# FM-Radio-Simple-Receiver-2.net
KiCad netlist of a schematic drawn in EAGLE
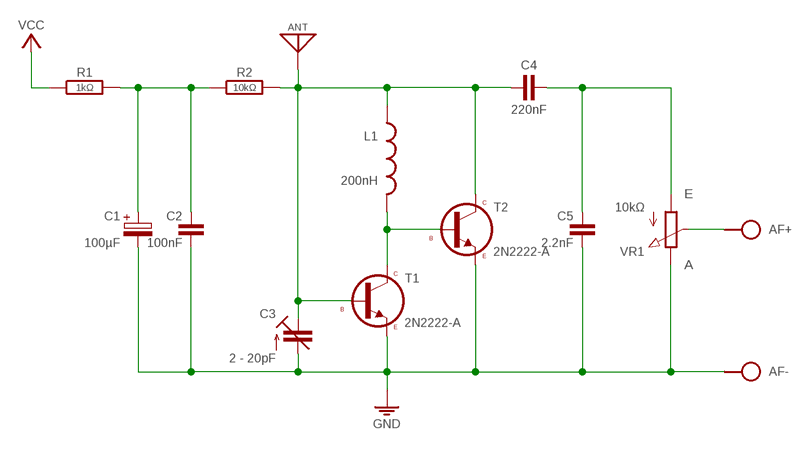
[diagram p0: schematic, sheet 1]

(export (version "E")
  (design (tool "Eeschema 10.0.6"))
  (components
    (comp (ref "AF")
      (value "SPAD+-+-")
      (footprint "eagle-import:SPAD+-")
      (libsource (lib "eagle-import") (part "SPAD+-+-"))
    )
    (comp (ref "ANT")
      (value "ANT")
      (footprint "eagle-import:SPAD")
      (libsource (lib "eagle-import") (part "ANT"))
    )
    (comp (ref "BAT")
      (value "VCC_GNDL")
      (footprint "eagle-import:SPAD-+")
      (libsource (lib "eagle-import") (part "VCC_GNDL"))
    )
    (comp (ref "C1")
      (value "100µF")
      (footprint "eagle-import:E2,5-5_V")
      (libsource (lib "eagle-import") (part "CPOLE2,5-5/V"))
    )
    (comp (ref "C2")
      (value "100nF")
      (footprint "eagle-import:C025-024X044")
      (libsource (lib "eagle-import") (part "C025-024X044"))
    )
    (comp (ref "C3")
      (value "2 - 20pF")
      (footprint "eagle-import:CTRIMBB")
      (libsource (lib "eagle-import") (part "C-TR-PH20127-2-1"))
    )
    (comp (ref "C4")
      (value "220nF")
      (footprint "eagle-import:C050-020X044")
      (libsource (lib "eagle-import") (part "C-H050-020X044"))
    )
    (comp (ref "C5")
      (value "2.2nF")
      (footprint "eagle-import:C050-020X036_V")
      (libsource (lib "eagle-import") (part "C050-020X036/V"))
    )
    (comp (ref "L1")
      (value "200nH")
      (footprint "eagle-import:L-10_10X")
      (libsource (lib "eagle-import") (part "L10/10X"))
    )
    (comp (ref "R1")
      (value "1kΩ")
      (footprint "eagle-import:0204_10-V")
      (libsource (lib "eagle-import") (part "R-H0204/10-V"))
    )
    (comp (ref "R2")
      (value "10kΩ")
      (footprint "eagle-import:0204_10-V")
      (libsource (lib "eagle-import") (part "R-H0204/10-V"))
    )
    (comp (ref "T1")
      (value "2N2222-A")
      (footprint "eagle-import:TO92-A")
      (libsource (lib "eagle-import") (part "2N2222-A"))
    )
    (comp (ref "T2")
      (value "2N2222-A")
      (footprint "eagle-import:TO92-A")
      (libsource (lib "eagle-import") (part "2N2222-A"))
    )
    (comp (ref "VR1")
      (value "10kΩ")
      (footprint "eagle-import:CONN-3P")
      (libsource (lib "eagle-import") (part "POT-3P"))
    )
  )
  (nets
    (net (code "1") (name "Net-(AFA-P$1)") (class "Default")
      (node (ref "AF") (pin "2") (pinfunction "P$1_2") (pintype "passive"))
      (node (ref "VR1") (pin "2") (pinfunction "S_2") (pintype "passive"))
    )
    (net (code "2") (name "Net-(AFB-P$1)") (class "Default")
      (node (ref "AF") (pin "1") (pinfunction "P$1_1") (pintype "passive"))
      (node (ref "BAT") (pin "1") (pinfunction "GND_1") (pintype "power_in"))
      (node (ref "C1") (pin "-") (pinfunction "-_-") (pintype "passive"))
      (node (ref "C2") (pin "2") (pinfunction "2_2") (pintype "passive"))
      (node (ref "C3") (pin "1") (pinfunction "A_1") (pintype "passive"))
      (node (ref "C5") (pin "2") (pinfunction "2_2") (pintype "passive"))
      (node (ref "T1") (pin "1") (pinfunction "E_1") (pintype "passive"))
      (node (ref "T2") (pin "1") (pinfunction "E_1") (pintype "passive"))
      (node (ref "VR1") (pin "3") (pinfunction "E_3") (pintype "passive"))
    )
    (net (code "3") (name "Net-(BATA-VCC)") (class "Default")
      (node (ref "BAT") (pin "2") (pinfunction "VCC_2") (pintype "power_in"))
      (node (ref "R1") (pin "1") (pinfunction "1_1") (pintype "passive"))
    )
    (net (code "4") (name "Net-(C1-Pad+)") (class "Default")
      (node (ref "C1") (pin "+") (pinfunction "+_+") (pintype "passive"))
      (node (ref "C2") (pin "1") (pinfunction "1_1") (pintype "passive"))
      (node (ref "R1") (pin "2") (pinfunction "2_2") (pintype "passive"))
      (node (ref "R2") (pin "1") (pinfunction "1_1") (pintype "passive"))
    )
    (net (code "5") (name "Net-(C3-E)") (class "Default")
      (node (ref "ANT") (pin "1") (pinfunction "1_1") (pintype "output"))
      (node (ref "C3") (pin "2") (pinfunction "E_2") (pintype "passive"))
      (node (ref "C4") (pin "1") (pinfunction "1_1") (pintype "passive"))
      (node (ref "L1") (pin "1") (pinfunction "1_1") (pintype "passive"))
      (node (ref "R2") (pin "2") (pinfunction "2_2") (pintype "passive"))
      (node (ref "T1") (pin "2") (pinfunction "B_2") (pintype "passive"))
      (node (ref "T2") (pin "3") (pinfunction "C_3") (pintype "passive"))
    )
    (net (code "6") (name "Net-(T1-C)") (class "Default")
      (node (ref "L1") (pin "2") (pinfunction "2_2") (pintype "passive"))
      (node (ref "T1") (pin "3") (pinfunction "C_3") (pintype "passive"))
      (node (ref "T2") (pin "2") (pinfunction "B_2") (pintype "passive"))
    )
    (net (code "7") (name "Net-(VR1-A)") (class "Default")
      (node (ref "C4") (pin "2") (pinfunction "2_2") (pintype "passive"))
      (node (ref "C5") (pin "1") (pinfunction "1_1") (pintype "passive"))
      (node (ref "VR1") (pin "1") (pinfunction "A_1") (pintype "passive"))
    )
  )
)
